# El-Fueradoro_Zuendbox.net
KiCad netlist of a schematic drawn in EAGLE
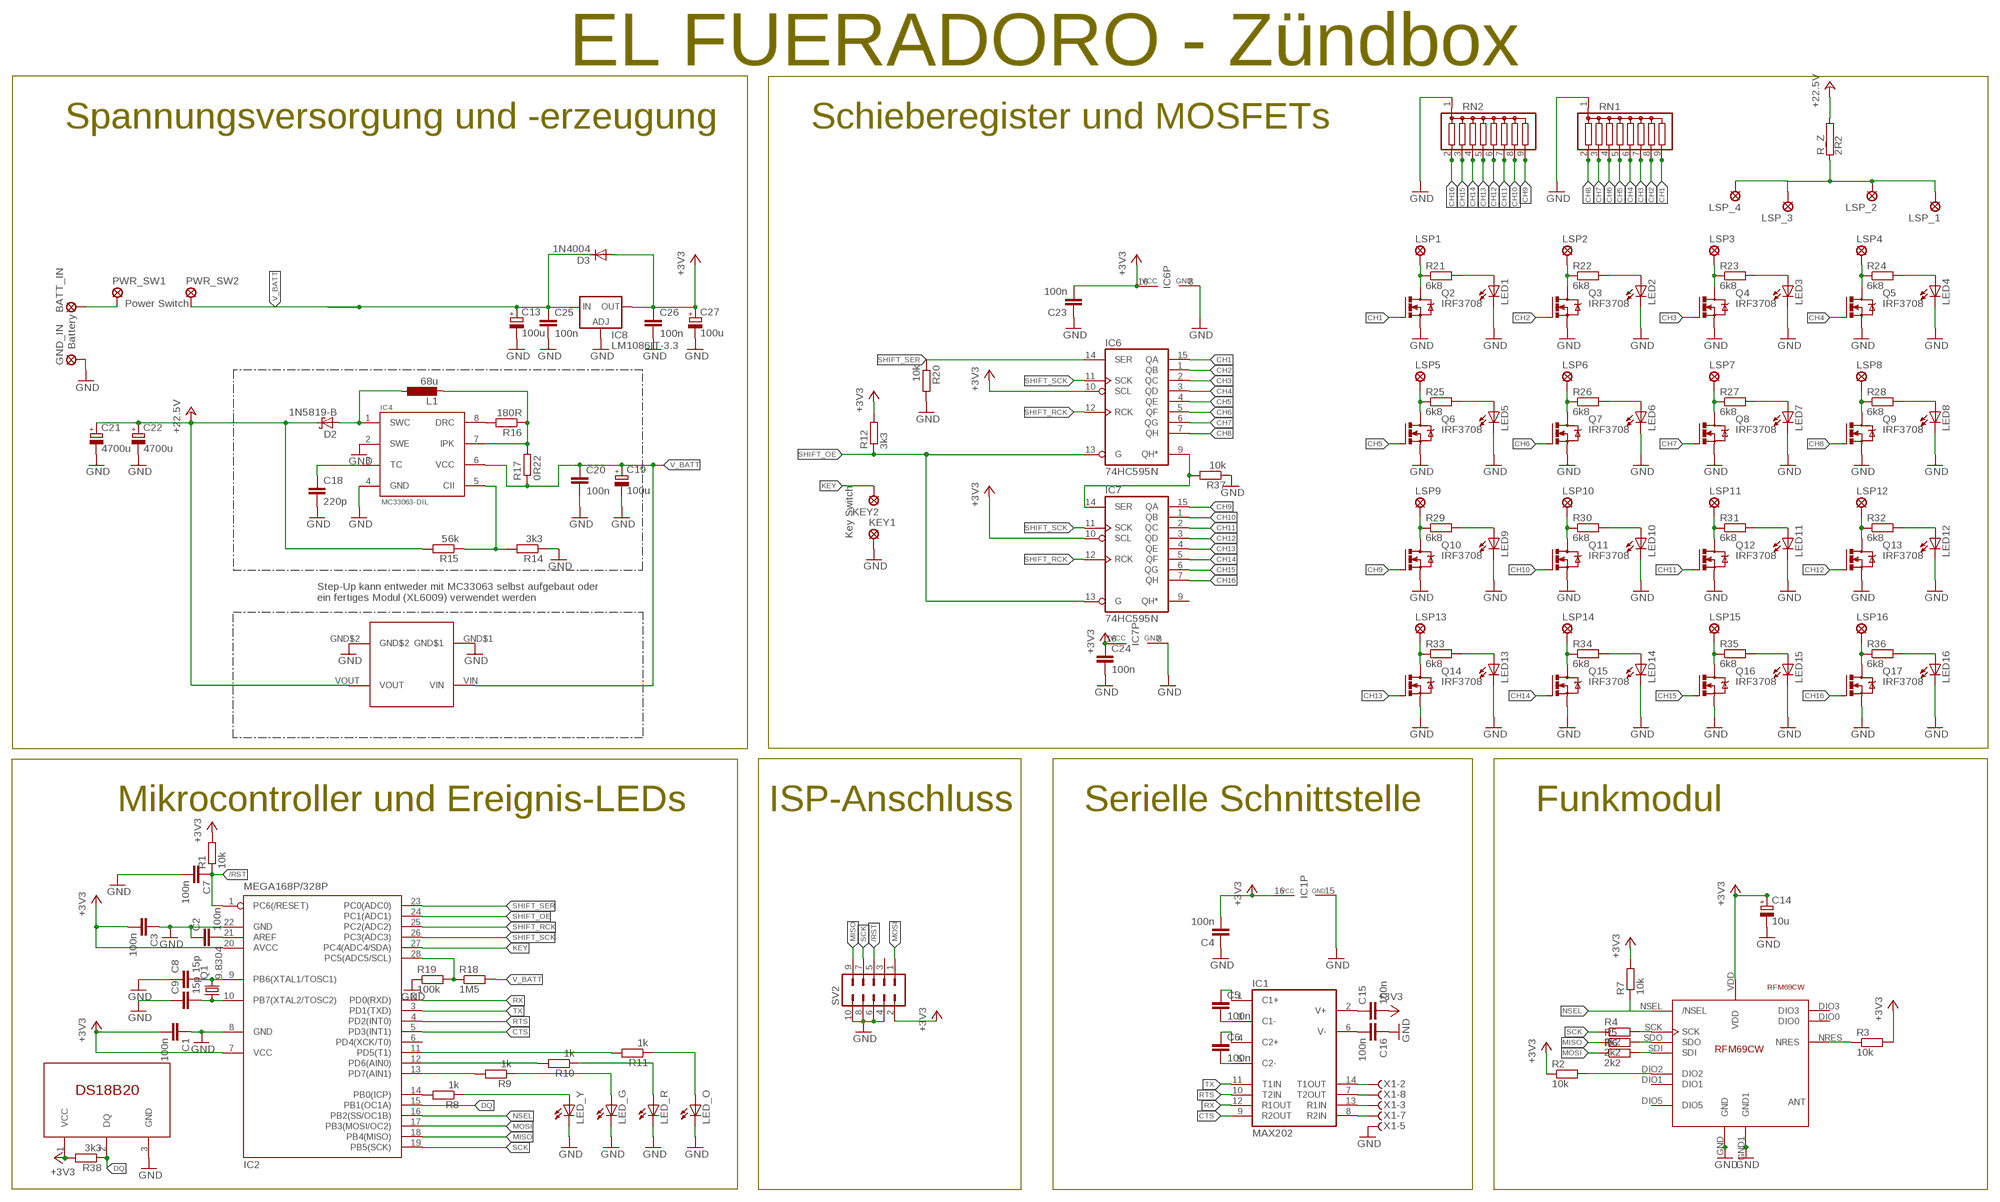
[diagram p0: schematic, sheet 1]

(export (version "E")
  (design (tool "Eeschema 10.0.6"))
  (components
    (comp (ref "BATT_IN")
      (value "LSP10")
      (footprint "eagle-import:LSP10")
      (libsource (lib "eagle-import") (part "LSP10"))
    )
    (comp (ref "C1")
      (value "100n")
      (footprint "eagle-import:C025-024X044")
      (libsource (lib "eagle-import") (part "C-EU025-024X044"))
    )
    (comp (ref "C2")
      (value "100n")
      (footprint "eagle-import:C025-024X044")
      (libsource (lib "eagle-import") (part "C-EU025-024X044"))
    )
    (comp (ref "C3")
      (value "100n")
      (footprint "eagle-import:C025-024X044")
      (libsource (lib "eagle-import") (part "C-EU025-024X044"))
    )
    (comp (ref "C4")
      (value "100n")
      (footprint "eagle-import:C025-024X044")
      (libsource (lib "eagle-import") (part "C-EU025-024X044"))
    )
    (comp (ref "C5")
      (value "100n")
      (footprint "eagle-import:C025-024X044")
      (libsource (lib "eagle-import") (part "C-EU025-024X044"))
    )
    (comp (ref "C6")
      (value "100n")
      (footprint "eagle-import:C025-024X044")
      (libsource (lib "eagle-import") (part "C-EU025-024X044"))
    )
    (comp (ref "C7")
      (value "100n")
      (footprint "eagle-import:C025-024X044")
      (libsource (lib "eagle-import") (part "C-EU025-024X044"))
    )
    (comp (ref "C8")
      (value "15p")
      (footprint "eagle-import:C025-024X044")
      (libsource (lib "eagle-import") (part "C-EU025-024X044"))
    )
    (comp (ref "C9")
      (value "15p")
      (footprint "eagle-import:C025-024X044")
      (libsource (lib "eagle-import") (part "C-EU025-024X044"))
    )
    (comp (ref "C13")
      (value "100u")
      (footprint "eagle-import:B45181A")
      (libsource (lib "eagle-import") (part "CPOL-EUB45181A"))
    )
    (comp (ref "C14")
      (value "10u")
      (footprint "eagle-import:B45181A")
      (libsource (lib "eagle-import") (part "CPOL-EUB45181A"))
    )
    (comp (ref "C15")
      (value "100n")
      (footprint "eagle-import:C025-024X044")
      (libsource (lib "eagle-import") (part "C-EU025-024X044"))
    )
    (comp (ref "C16")
      (value "100n")
      (footprint "eagle-import:C025-024X044")
      (libsource (lib "eagle-import") (part "C-EU025-024X044"))
    )
    (comp (ref "C18")
      (value "220p")
      (footprint "eagle-import:C025-024X044")
      (libsource (lib "eagle-import") (part "C-EU025-024X044"))
    )
    (comp (ref "C19")
      (value "100u")
      (footprint "eagle-import:E2,5-6E")
      (libsource (lib "eagle-import") (part "CPOL-EUE2,5-6E"))
    )
    (comp (ref "C20")
      (value "100n")
      (footprint "eagle-import:C025-024X044")
      (libsource (lib "eagle-import") (part "C-EU025-024X044"))
    )
    (comp (ref "C21")
      (value "4700u")
      (footprint "eagle-import:E7,5-18")
      (libsource (lib "eagle-import") (part "CPOL-EUE7.5-18"))
    )
    (comp (ref "C22")
      (value "4700u")
      (footprint "eagle-import:E7,5-18")
      (libsource (lib "eagle-import") (part "CPOL-EUE7.5-18"))
    )
    (comp (ref "C23")
      (value "100n")
      (footprint "eagle-import:C025-024X044")
      (libsource (lib "eagle-import") (part "C-EU025-024X044"))
    )
    (comp (ref "C24")
      (value "100n")
      (footprint "eagle-import:C025-024X044")
      (libsource (lib "eagle-import") (part "C-EU025-024X044"))
    )
    (comp (ref "C25")
      (value "100n")
      (footprint "eagle-import:C025-024X044")
      (libsource (lib "eagle-import") (part "C-EU025-024X044"))
    )
    (comp (ref "C26")
      (value "100n")
      (footprint "eagle-import:C025-024X044")
      (libsource (lib "eagle-import") (part "C-EU025-024X044"))
    )
    (comp (ref "C27")
      (value "100u")
      (footprint "eagle-import:B45181A")
      (libsource (lib "eagle-import") (part "CPOL-EUB45181A"))
    )
    (comp (ref "D2")
      (value "1N5819-B")
      (footprint "eagle-import:DO41-7.6")
      (libsource (lib "eagle-import") (part "1N5819-B"))
    )
    (comp (ref "D3")
      (value "1N4004")
      (footprint "eagle-import:DO41-10")
      (libsource (lib "eagle-import") (part "1N4004"))
    )
    (comp (ref "GND_IN")
      (value "LSP10")
      (footprint "eagle-import:LSP10")
      (libsource (lib "eagle-import") (part "LSP10"))
    )
    (comp (ref "IC1")
      (value "MAX202")
      (footprint "eagle-import:DIL16")
      (fields (field (name "MF") "MAXIM") (field (name "MPN") "MAX232ACPE+"))
      (libsource (lib "eagle-import") (part "MAX232"))
    )
    (comp (ref "IC2")
      (value "MEGA168P/328P")
      (footprint "eagle-import:DIL28-3")
      (libsource (lib "eagle-import") (part "MEGA8-P"))
    )
    (comp (ref "IC4")
      (value "MC33063-DIL")
      (footprint "eagle-import:DIL08")
      (libsource (lib "eagle-import") (part "MC34063-DIL"))
    )
    (comp (ref "IC6")
      (value "74HC595N")
      (footprint "eagle-import:DIL16")
      (libsource (lib "eagle-import") (part "74595NHC"))
    )
    (comp (ref "IC7")
      (value "74HC595N")
      (footprint "eagle-import:DIL16")
      (libsource (lib "eagle-import") (part "74595NHC"))
    )
    (comp (ref "IC8")
      (value "LM1086IT-3.3")
      (footprint "eagle-import:TO220L1")
      (libsource (lib "eagle-import") (part "LD117A?V"))
    )
    (comp (ref "KEY1")
      (value "LSP10")
      (footprint "eagle-import:LSP10")
      (libsource (lib "eagle-import") (part "LSP10"))
    )
    (comp (ref "KEY2")
      (value "LSP10")
      (footprint "eagle-import:LSP10")
      (libsource (lib "eagle-import") (part "LSP10"))
    )
    (comp (ref "L1")
      (value "68u")
      (footprint "eagle-import:0204_5")
      (libsource (lib "eagle-import") (part "L-EU0204/5"))
    )
    (comp (ref "LED1")
      (value "LED3MM")
      (footprint "eagle-import:LED3MM")
      (libsource (lib "eagle-import") (part "LED3MM"))
    )
    (comp (ref "LED2")
      (value "LED3MM")
      (footprint "eagle-import:LED3MM")
      (libsource (lib "eagle-import") (part "LED3MM"))
    )
    (comp (ref "LED3")
      (value "LED3MM")
      (footprint "eagle-import:LED3MM")
      (libsource (lib "eagle-import") (part "LED3MM"))
    )
    (comp (ref "LED4")
      (value "LED3MM")
      (footprint "eagle-import:LED3MM")
      (libsource (lib "eagle-import") (part "LED3MM"))
    )
    (comp (ref "LED5")
      (value "LED3MM")
      (footprint "eagle-import:LED3MM")
      (libsource (lib "eagle-import") (part "LED3MM"))
    )
    (comp (ref "LED6")
      (value "LED3MM")
      (footprint "eagle-import:LED3MM")
      (libsource (lib "eagle-import") (part "LED3MM"))
    )
    (comp (ref "LED7")
      (value "LED3MM")
      (footprint "eagle-import:LED3MM")
      (libsource (lib "eagle-import") (part "LED3MM"))
    )
    (comp (ref "LED8")
      (value "LED3MM")
      (footprint "eagle-import:LED3MM")
      (libsource (lib "eagle-import") (part "LED3MM"))
    )
    (comp (ref "LED9")
      (value "LED3MM")
      (footprint "eagle-import:LED3MM")
      (libsource (lib "eagle-import") (part "LED3MM"))
    )
    (comp (ref "LED10")
      (value "LED3MM")
      (footprint "eagle-import:LED3MM")
      (libsource (lib "eagle-import") (part "LED3MM"))
    )
    (comp (ref "LED11")
      (value "LED3MM")
      (footprint "eagle-import:LED3MM")
      (libsource (lib "eagle-import") (part "LED3MM"))
    )
    (comp (ref "LED12")
      (value "LED3MM")
      (footprint "eagle-import:LED3MM")
      (libsource (lib "eagle-import") (part "LED3MM"))
    )
    (comp (ref "LED13")
      (value "LED3MM")
      (footprint "eagle-import:LED3MM")
      (libsource (lib "eagle-import") (part "LED3MM"))
    )
    (comp (ref "LED14")
      (value "LED3MM")
      (footprint "eagle-import:LED3MM")
      (libsource (lib "eagle-import") (part "LED3MM"))
    )
    (comp (ref "LED15")
      (value "LED3MM")
      (footprint "eagle-import:LED3MM")
      (libsource (lib "eagle-import") (part "LED3MM"))
    )
    (comp (ref "LED16")
      (value "LED3MM")
      (footprint "eagle-import:LED3MM")
      (libsource (lib "eagle-import") (part "LED3MM"))
    )
    (comp (ref "LED_G")
      (value "LED5MM")
      (footprint "eagle-import:LED5MM")
      (libsource (lib "eagle-import") (part "LED5MM"))
    )
    (comp (ref "LED_O")
      (value "LED5MM")
      (footprint "eagle-import:LED5MM")
      (libsource (lib "eagle-import") (part "LED5MM"))
    )
    (comp (ref "LED_R")
      (value "LED5MM")
      (footprint "eagle-import:LED5MM")
      (libsource (lib "eagle-import") (part "LED5MM"))
    )
    (comp (ref "LED_Y")
      (value "LED5MM")
      (footprint "eagle-import:LED5MM")
      (libsource (lib "eagle-import") (part "LED5MM"))
    )
    (comp (ref "LSP1")
      (value "LSP11")
      (footprint "eagle-import:LSP11")
      (libsource (lib "eagle-import") (part "LSP11"))
    )
    (comp (ref "LSP2")
      (value "LSP11")
      (footprint "eagle-import:LSP11")
      (libsource (lib "eagle-import") (part "LSP11"))
    )
    (comp (ref "LSP3")
      (value "LSP11")
      (footprint "eagle-import:LSP11")
      (libsource (lib "eagle-import") (part "LSP11"))
    )
    (comp (ref "LSP4")
      (value "LSP11")
      (footprint "eagle-import:LSP11")
      (libsource (lib "eagle-import") (part "LSP11"))
    )
    (comp (ref "LSP5")
      (value "LSP11")
      (footprint "eagle-import:LSP11")
      (libsource (lib "eagle-import") (part "LSP11"))
    )
    (comp (ref "LSP6")
      (value "LSP11")
      (footprint "eagle-import:LSP11")
      (libsource (lib "eagle-import") (part "LSP11"))
    )
    (comp (ref "LSP7")
      (value "LSP11")
      (footprint "eagle-import:LSP11")
      (libsource (lib "eagle-import") (part "LSP11"))
    )
    (comp (ref "LSP8")
      (value "LSP11")
      (footprint "eagle-import:LSP11")
      (libsource (lib "eagle-import") (part "LSP11"))
    )
    (comp (ref "LSP9")
      (value "LSP11")
      (footprint "eagle-import:LSP11")
      (libsource (lib "eagle-import") (part "LSP11"))
    )
    (comp (ref "LSP10")
      (value "LSP11")
      (footprint "eagle-import:LSP11")
      (libsource (lib "eagle-import") (part "LSP11"))
    )
    (comp (ref "LSP11")
      (value "LSP11")
      (footprint "eagle-import:LSP11")
      (libsource (lib "eagle-import") (part "LSP11"))
    )
    (comp (ref "LSP12")
      (value "LSP11")
      (footprint "eagle-import:LSP11")
      (libsource (lib "eagle-import") (part "LSP11"))
    )
    (comp (ref "LSP13")
      (value "LSP11")
      (footprint "eagle-import:LSP11")
      (libsource (lib "eagle-import") (part "LSP11"))
    )
    (comp (ref "LSP14")
      (value "LSP11")
      (footprint "eagle-import:LSP11")
      (libsource (lib "eagle-import") (part "LSP11"))
    )
    (comp (ref "LSP15")
      (value "LSP11")
      (footprint "eagle-import:LSP11")
      (libsource (lib "eagle-import") (part "LSP11"))
    )
    (comp (ref "LSP16")
      (value "LSP11")
      (footprint "eagle-import:LSP11")
      (libsource (lib "eagle-import") (part "LSP11"))
    )
    (comp (ref "LSP_1")
      (value "LSP11")
      (footprint "eagle-import:LSP11")
      (libsource (lib "eagle-import") (part "LSP11"))
    )
    (comp (ref "LSP_2")
      (value "LSP11")
      (footprint "eagle-import:LSP11")
      (libsource (lib "eagle-import") (part "LSP11"))
    )
    (comp (ref "LSP_3")
      (value "LSP11")
      (footprint "eagle-import:LSP11")
      (libsource (lib "eagle-import") (part "LSP11"))
    )
    (comp (ref "LSP_4")
      (value "LSP11")
      (footprint "eagle-import:LSP11")
      (libsource (lib "eagle-import") (part "LSP11"))
    )
    (comp (ref "PWR_SW1")
      (value "LSP10")
      (footprint "eagle-import:LSP10")
      (libsource (lib "eagle-import") (part "LSP10"))
    )
    (comp (ref "PWR_SW2")
      (value "LSP10")
      (footprint "eagle-import:LSP10")
      (libsource (lib "eagle-import") (part "LSP10"))
    )
    (comp (ref "Q1")
      (value "9.8304")
      (footprint "eagle-import:HC49_S")
      (libsource (lib "eagle-import") (part "CRYSTALHC49S"))
    )
    (comp (ref "Q2")
      (value "IRF3708")
      (footprint "eagle-import:TO220BV")
      (libsource (lib "eagle-import") (part "IRF530"))
    )
    (comp (ref "Q3")
      (value "IRF3708")
      (footprint "eagle-import:TO220BV")
      (libsource (lib "eagle-import") (part "IRF530"))
    )
    (comp (ref "Q4")
      (value "IRF3708")
      (footprint "eagle-import:TO220BV")
      (libsource (lib "eagle-import") (part "IRF530"))
    )
    (comp (ref "Q5")
      (value "IRF3708")
      (footprint "eagle-import:TO220BV")
      (libsource (lib "eagle-import") (part "IRF530"))
    )
    (comp (ref "Q6")
      (value "IRF3708")
      (footprint "eagle-import:TO220BV")
      (libsource (lib "eagle-import") (part "IRF530"))
    )
    (comp (ref "Q7")
      (value "IRF3708")
      (footprint "eagle-import:TO220BV")
      (libsource (lib "eagle-import") (part "IRF530"))
    )
    (comp (ref "Q8")
      (value "IRF3708")
      (footprint "eagle-import:TO220BV")
      (libsource (lib "eagle-import") (part "IRF530"))
    )
    (comp (ref "Q9")
      (value "IRF3708")
      (footprint "eagle-import:TO220BV")
      (libsource (lib "eagle-import") (part "IRF530"))
    )
    (comp (ref "Q10")
      (value "IRF3708")
      (footprint "eagle-import:TO220BV")
      (libsource (lib "eagle-import") (part "IRF530"))
    )
    (comp (ref "Q11")
      (value "IRF3708")
      (footprint "eagle-import:TO220BV")
      (libsource (lib "eagle-import") (part "IRF530"))
    )
    (comp (ref "Q12")
      (value "IRF3708")
      (footprint "eagle-import:TO220BV")
      (libsource (lib "eagle-import") (part "IRF530"))
    )
    (comp (ref "Q13")
      (value "IRF3708")
      (footprint "eagle-import:TO220BV")
      (libsource (lib "eagle-import") (part "IRF530"))
    )
    (comp (ref "Q14")
      (value "IRF3708")
      (footprint "eagle-import:TO220BV")
      (libsource (lib "eagle-import") (part "IRF530"))
    )
    (comp (ref "Q15")
      (value "IRF3708")
      (footprint "eagle-import:TO220BV")
      (libsource (lib "eagle-import") (part "IRF530"))
    )
    (comp (ref "Q16")
      (value "IRF3708")
      (footprint "eagle-import:TO220BV")
      (libsource (lib "eagle-import") (part "IRF530"))
    )
    (comp (ref "Q17")
      (value "IRF3708")
      (footprint "eagle-import:TO220BV")
      (libsource (lib "eagle-import") (part "IRF530"))
    )
    (comp (ref "R1")
      (value "10k")
      (footprint "eagle-import:0207_10")
      (libsource (lib "eagle-import") (part "R-EU_0207/10"))
    )
    (comp (ref "R2")
      (value "10k")
      (footprint "eagle-import:0207_10")
      (libsource (lib "eagle-import") (part "R-EU_0207/10"))
    )
    (comp (ref "R3")
      (value "10k")
      (footprint "eagle-import:0207_10")
      (libsource (lib "eagle-import") (part "R-EU_0207/10"))
    )
    (comp (ref "R4")
      (value "2k2")
      (footprint "eagle-import:0207_10")
      (libsource (lib "eagle-import") (part "R-EU_0207/10"))
    )
    (comp (ref "R5")
      (value "2k2")
      (footprint "eagle-import:0207_10")
      (libsource (lib "eagle-import") (part "R-EU_0207/10"))
    )
    (comp (ref "R6")
      (value "2k2")
      (footprint "eagle-import:0207_10")
      (libsource (lib "eagle-import") (part "R-EU_0207/10"))
    )
    (comp (ref "R7")
      (value "10k")
      (footprint "eagle-import:0207_10")
      (libsource (lib "eagle-import") (part "R-EU_0207/10"))
    )
    (comp (ref "R8")
      (value "1k")
      (footprint "eagle-import:0207_10")
      (libsource (lib "eagle-import") (part "R-EU_0207/10"))
    )
    (comp (ref "R9")
      (value "1k")
      (footprint "eagle-import:0207_10")
      (libsource (lib "eagle-import") (part "R-EU_0207/10"))
    )
    (comp (ref "R10")
      (value "1k")
      (footprint "eagle-import:0207_10")
      (libsource (lib "eagle-import") (part "R-EU_0207/10"))
    )
    (comp (ref "R11")
      (value "1k")
      (footprint "eagle-import:0207_10")
      (libsource (lib "eagle-import") (part "R-EU_0207/10"))
    )
    (comp (ref "R12")
      (value "3k3")
      (footprint "eagle-import:0207_10")
      (libsource (lib "eagle-import") (part "R-EU_0207/10"))
    )
    (comp (ref "R14")
      (value "3k3")
      (footprint "eagle-import:0207_10")
      (libsource (lib "eagle-import") (part "R-EU_0207/10"))
    )
    (comp (ref "R15")
      (value "56k")
      (footprint "eagle-import:0207_10")
      (libsource (lib "eagle-import") (part "R-EU_0207/10"))
    )
    (comp (ref "R16")
      (value "180R")
      (footprint "eagle-import:0207_10")
      (libsource (lib "eagle-import") (part "R-EU_0207/10"))
    )
    (comp (ref "R17")
      (value "0R22")
      (footprint "eagle-import:0207_10")
      (libsource (lib "eagle-import") (part "R-EU_0207/10"))
    )
    (comp (ref "R18")
      (value "1M5")
      (footprint "eagle-import:0207_10")
      (libsource (lib "eagle-import") (part "R-EU_0207/10"))
    )
    (comp (ref "R19")
      (value "100k")
      (footprint "eagle-import:0207_10")
      (libsource (lib "eagle-import") (part "R-EU_0207/10"))
    )
    (comp (ref "R20")
      (value "10k")
      (footprint "eagle-import:0207_10")
      (libsource (lib "eagle-import") (part "R-EU_0207/10"))
    )
    (comp (ref "R21")
      (value "6k8")
      (footprint "eagle-import:0207_10")
      (libsource (lib "eagle-import") (part "R-EU_0207/10"))
    )
    (comp (ref "R22")
      (value "6k8")
      (footprint "eagle-import:0207_10")
      (libsource (lib "eagle-import") (part "R-EU_0207/10"))
    )
    (comp (ref "R23")
      (value "6k8")
      (footprint "eagle-import:0207_10")
      (libsource (lib "eagle-import") (part "R-EU_0207/10"))
    )
    (comp (ref "R24")
      (value "6k8")
      (footprint "eagle-import:0207_10")
      (libsource (lib "eagle-import") (part "R-EU_0207/10"))
    )
    (comp (ref "R25")
      (value "6k8")
      (footprint "eagle-import:0207_10")
      (libsource (lib "eagle-import") (part "R-EU_0207/10"))
    )
    (comp (ref "R26")
      (value "6k8")
      (footprint "eagle-import:0207_10")
      (libsource (lib "eagle-import") (part "R-EU_0207/10"))
    )
    (comp (ref "R27")
      (value "6k8")
      (footprint "eagle-import:0207_10")
      (libsource (lib "eagle-import") (part "R-EU_0207/10"))
    )
    (comp (ref "R28")
      (value "6k8")
      (footprint "eagle-import:0207_10")
      (libsource (lib "eagle-import") (part "R-EU_0207/10"))
    )
    (comp (ref "R29")
      (value "6k8")
      (footprint "eagle-import:0207_10")
      (libsource (lib "eagle-import") (part "R-EU_0207/10"))
    )
    (comp (ref "R30")
      (value "6k8")
      (footprint "eagle-import:0207_10")
      (libsource (lib "eagle-import") (part "R-EU_0207/10"))
    )
    (comp (ref "R31")
      (value "6k8")
      (footprint "eagle-import:0207_10")
      (libsource (lib "eagle-import") (part "R-EU_0207/10"))
    )
    (comp (ref "R32")
      (value "6k8")
      (footprint "eagle-import:0207_10")
      (libsource (lib "eagle-import") (part "R-EU_0207/10"))
    )
    (comp (ref "R33")
      (value "6k8")
      (footprint "eagle-import:0207_10")
      (libsource (lib "eagle-import") (part "R-EU_0207/10"))
    )
    (comp (ref "R34")
      (value "6k8")
      (footprint "eagle-import:0207_10")
      (libsource (lib "eagle-import") (part "R-EU_0207/10"))
    )
    (comp (ref "R35")
      (value "6k8")
      (footprint "eagle-import:0207_10")
      (libsource (lib "eagle-import") (part "R-EU_0207/10"))
    )
    (comp (ref "R36")
      (value "6k8")
      (footprint "eagle-import:0207_10")
      (libsource (lib "eagle-import") (part "R-EU_0207/10"))
    )
    (comp (ref "R37")
      (value "10k")
      (footprint "eagle-import:0207_10")
      (libsource (lib "eagle-import") (part "R-EU_0207/10"))
    )
    (comp (ref "R38")
      (value "3k3")
      (footprint "eagle-import:0207_10")
      (libsource (lib "eagle-import") (part "R-EU_0207/10"))
    )
    (comp (ref "RN1")
      (value "G08R")
      (footprint "eagle-import:SIL9")
      (libsource (lib "eagle-import") (part "G08R"))
    )
    (comp (ref "RN2")
      (value "G08R")
      (footprint "eagle-import:SIL9")
      (libsource (lib "eagle-import") (part "G08R"))
    )
    (comp (ref "R_Z")
      (value "2R2")
      (footprint "eagle-import:KH214R-8")
      (libsource (lib "eagle-import") (part "RKH214-8R"))
    )
    (comp (ref "SV2")
      (value "ML10")
      (footprint "eagle-import:ML10")
      (libsource (lib "eagle-import") (part "ML10"))
    )
    (comp (ref "U$2")
      (value "DS18B20")
      (footprint "eagle-import:TO92-LINE")
      (libsource (lib "eagle-import") (part "DS18B20"))
    )
    (comp (ref "U$3")
      (value "XL6009_MODULED")
      (footprint "eagle-import:XL6009_PACK")
      (libsource (lib "eagle-import") (part "XL6009_MODULED"))
    )
    (comp (ref "U$4")
      (value "RFM69CW")
      (footprint "eagle-import:RFM69CW")
      (libsource (lib "eagle-import") (part "RFM69CW"))
    )
    (comp (ref "X1")
      (value "F09HPS")
      (footprint "eagle-import:F09HP")
      (libsource (lib "eagle-import") (part "F09HPS"))
    )
  )
  (nets
    (net (code "1") (name "+3V3") (class "Default")
      (node (ref "C1") (pin "2") (pinfunction "2_2") (pintype "passive"))
      (node (ref "C14") (pin "+") (pinfunction "+_+") (pintype "passive"))
      (node (ref "C15") (pin "2") (pinfunction "2_2") (pintype "passive"))
      (node (ref "C23") (pin "2") (pinfunction "2_2") (pintype "passive"))
      (node (ref "C24") (pin "1") (pinfunction "1_1") (pintype "passive"))
      (node (ref "C26") (pin "1") (pinfunction "1_1") (pintype "passive"))
      (node (ref "C27") (pin "+") (pinfunction "+_+") (pintype "passive"))
      (node (ref "C3") (pin "2") (pinfunction "2_2") (pintype "passive"))
      (node (ref "C4") (pin "2") (pinfunction "2_2") (pintype "passive"))
      (node (ref "D3") (pin "A") (pinfunction "A_A") (pintype "passive"))
      (node (ref "IC1") (pin "16") (pinfunction "VCC_16") (pintype "power_in"))
      (node (ref "IC2") (pin "20") (pinfunction "AVCC_20") (pintype "power_in"))
      (node (ref "IC2") (pin "7") (pinfunction "VCC_7") (pintype "power_in"))
      (node (ref "IC6") (pin "10") (pinfunction "SCL_10") (pintype "input"))
      (node (ref "IC6") (pin "16") (pinfunction "VCC_16") (pintype "power_in"))
      (node (ref "IC7") (pin "10") (pinfunction "SCL_10") (pintype "input"))
      (node (ref "IC7") (pin "16") (pinfunction "VCC_16") (pintype "power_in"))
      (node (ref "IC8") (pin "2") (pinfunction "OUT_2") (pintype "passive"))
      (node (ref "R1") (pin "2") (pinfunction "2_2") (pintype "passive"))
      (node (ref "R12") (pin "2") (pinfunction "2_2") (pintype "passive"))
      (node (ref "R2") (pin "1") (pinfunction "1_1") (pintype "passive"))
      (node (ref "R3") (pin "2") (pinfunction "2_2") (pintype "passive"))
      (node (ref "R38") (pin "2") (pinfunction "2_2") (pintype "passive"))
      (node (ref "R7") (pin "2") (pinfunction "2_2") (pintype "passive"))
      (node (ref "SV2") (pin "2") (pinfunction "2_2") (pintype "passive"))
      (node (ref "U$2") (pin "1") (pinfunction "VCC_1") (pintype "power_in"))
      (node (ref "U$4") (pin "VDD") (pinfunction "VDD_VDD") (pintype "power_in"))
    )
    (net (code "2") (name "+22.5V") (class "Default")
      (node (ref "C21") (pin "+") (pinfunction "+_+") (pintype "passive"))
      (node (ref "C22") (pin "+") (pinfunction "+_+") (pintype "passive"))
      (node (ref "D2") (pin "C") (pinfunction "C_C") (pintype "passive"))
      (node (ref "R15") (pin "2") (pinfunction "2_2") (pintype "passive"))
      (node (ref "R_Z") (pin "2") (pinfunction "2_2") (pintype "passive"))
      (node (ref "U$3") (pin "VOUT") (pinfunction "VOUT_VOUT") (pintype "bidirectional"))
    )
    (net (code "3") (name "CH1") (class "Default")
      (node (ref "IC6") (pin "15") (pinfunction "QA_15") (pintype "tri_state"))
      (node (ref "Q2") (pin "G") (pinfunction "G_G") (pintype "passive"))
      (node (ref "RN1") (pin "9") (pinfunction "9_9") (pintype "passive"))
    )
    (net (code "4") (name "CH2") (class "Default")
      (node (ref "IC6") (pin "1") (pinfunction "QB_1") (pintype "tri_state"))
      (node (ref "Q3") (pin "G") (pinfunction "G_G") (pintype "passive"))
      (node (ref "RN1") (pin "8") (pinfunction "8_8") (pintype "passive"))
    )
    (net (code "5") (name "CH3") (class "Default")
      (node (ref "IC6") (pin "2") (pinfunction "QC_2") (pintype "tri_state"))
      (node (ref "Q4") (pin "G") (pinfunction "G_G") (pintype "passive"))
      (node (ref "RN1") (pin "7") (pinfunction "7_7") (pintype "passive"))
    )
    (net (code "6") (name "CH4") (class "Default")
      (node (ref "IC6") (pin "3") (pinfunction "QD_3") (pintype "tri_state"))
      (node (ref "Q5") (pin "G") (pinfunction "G_G") (pintype "passive"))
      (node (ref "RN1") (pin "6") (pinfunction "6_6") (pintype "passive"))
    )
    (net (code "7") (name "CH5") (class "Default")
      (node (ref "IC6") (pin "4") (pinfunction "QE_4") (pintype "tri_state"))
      (node (ref "Q6") (pin "G") (pinfunction "G_G") (pintype "passive"))
      (node (ref "RN1") (pin "5") (pinfunction "5_5") (pintype "passive"))
    )
    (net (code "8") (name "CH6") (class "Default")
      (node (ref "IC6") (pin "5") (pinfunction "QF_5") (pintype "tri_state"))
      (node (ref "Q7") (pin "G") (pinfunction "G_G") (pintype "passive"))
      (node (ref "RN1") (pin "4") (pinfunction "4_4") (pintype "passive"))
    )
    (net (code "9") (name "CH7") (class "Default")
      (node (ref "IC6") (pin "6") (pinfunction "QG_6") (pintype "tri_state"))
      (node (ref "Q8") (pin "G") (pinfunction "G_G") (pintype "passive"))
      (node (ref "RN1") (pin "3") (pinfunction "3_3") (pintype "passive"))
    )
    (net (code "10") (name "CH8") (class "Default")
      (node (ref "IC6") (pin "7") (pinfunction "QH_7") (pintype "tri_state"))
      (node (ref "Q9") (pin "G") (pinfunction "G_G") (pintype "passive"))
      (node (ref "RN1") (pin "2") (pinfunction "2_2") (pintype "passive"))
    )
    (net (code "11") (name "CH9") (class "Default")
      (node (ref "IC7") (pin "15") (pinfunction "QA_15") (pintype "tri_state"))
      (node (ref "Q10") (pin "G") (pinfunction "G_G") (pintype "passive"))
      (node (ref "RN2") (pin "9") (pinfunction "9_9") (pintype "passive"))
    )
    (net (code "12") (name "CH10") (class "Default")
      (node (ref "IC7") (pin "1") (pinfunction "QB_1") (pintype "tri_state"))
      (node (ref "Q11") (pin "G") (pinfunction "G_G") (pintype "passive"))
      (node (ref "RN2") (pin "8") (pinfunction "8_8") (pintype "passive"))
    )
    (net (code "13") (name "CH11") (class "Default")
      (node (ref "IC7") (pin "2") (pinfunction "QC_2") (pintype "tri_state"))
      (node (ref "Q12") (pin "G") (pinfunction "G_G") (pintype "passive"))
      (node (ref "RN2") (pin "7") (pinfunction "7_7") (pintype "passive"))
    )
    (net (code "14") (name "CH12") (class "Default")
      (node (ref "IC7") (pin "3") (pinfunction "QD_3") (pintype "tri_state"))
      (node (ref "Q13") (pin "G") (pinfunction "G_G") (pintype "passive"))
      (node (ref "RN2") (pin "6") (pinfunction "6_6") (pintype "passive"))
    )
    (net (code "15") (name "CH13") (class "Default")
      (node (ref "IC7") (pin "4") (pinfunction "QE_4") (pintype "tri_state"))
      (node (ref "Q14") (pin "G") (pinfunction "G_G") (pintype "passive"))
      (node (ref "RN2") (pin "5") (pinfunction "5_5") (pintype "passive"))
    )
    (net (code "16") (name "CH14") (class "Default")
      (node (ref "IC7") (pin "5") (pinfunction "QF_5") (pintype "tri_state"))
      (node (ref "Q15") (pin "G") (pinfunction "G_G") (pintype "passive"))
      (node (ref "RN2") (pin "4") (pinfunction "4_4") (pintype "passive"))
    )
    (net (code "17") (name "CH15") (class "Default")
      (node (ref "IC7") (pin "6") (pinfunction "QG_6") (pintype "tri_state"))
      (node (ref "Q16") (pin "G") (pinfunction "G_G") (pintype "passive"))
      (node (ref "RN2") (pin "3") (pinfunction "3_3") (pintype "passive"))
    )
    (net (code "18") (name "CH16") (class "Default")
      (node (ref "IC7") (pin "7") (pinfunction "QH_7") (pintype "tri_state"))
      (node (ref "Q17") (pin "G") (pinfunction "G_G") (pintype "passive"))
      (node (ref "RN2") (pin "2") (pinfunction "2_2") (pintype "passive"))
    )
    (net (code "19") (name "CTS") (class "Default")
      (node (ref "IC1") (pin "9") (pinfunction "R2OUT_9") (pintype "output"))
      (node (ref "IC2") (pin "5") (pinfunction "PD3(INT1)_5") (pintype "bidirectional"))
    )
    (net (code "20") (name "DQ") (class "Default")
      (node (ref "IC2") (pin "15") (pinfunction "PB1(OC1A)_15") (pintype "bidirectional"))
      (node (ref "R38") (pin "1") (pinfunction "1_1") (pintype "passive"))
      (node (ref "U$2") (pin "2") (pinfunction "DQ_2") (pintype "bidirectional"))
    )
    (net (code "21") (name "GND") (class "Default")
      (node (ref "C1") (pin "1") (pinfunction "1_1") (pintype "passive"))
      (node (ref "C13") (pin "-") (pinfunction "-_-") (pintype "passive"))
      (node (ref "C14") (pin "-") (pinfunction "-_-") (pintype "passive"))
      (node (ref "C16") (pin "1") (pinfunction "1_1") (pintype "passive"))
      (node (ref "C18") (pin "2") (pinfunction "2_2") (pintype "passive"))
      (node (ref "C19") (pin "-") (pinfunction "-_-") (pintype "passive"))
      (node (ref "C2") (pin "1") (pinfunction "1_1") (pintype "passive"))
      (node (ref "C20") (pin "2") (pinfunction "2_2") (pintype "passive"))
      (node (ref "C21") (pin "-") (pinfunction "-_-") (pintype "passive"))
      (node (ref "C22") (pin "-") (pinfunction "-_-") (pintype "passive"))
      (node (ref "C23") (pin "1") (pinfunction "1_1") (pintype "passive"))
      (node (ref "C24") (pin "2") (pinfunction "2_2") (pintype "passive"))
      (node (ref "C25") (pin "2") (pinfunction "2_2") (pintype "passive"))
      (node (ref "C26") (pin "2") (pinfunction "2_2") (pintype "passive"))
      (node (ref "C27") (pin "-") (pinfunction "-_-") (pintype "passive"))
      (node (ref "C3") (pin "1") (pinfunction "1_1") (pintype "passive"))
      (node (ref "C4") (pin "1") (pinfunction "1_1") (pintype "passive"))
      (node (ref "C7") (pin "2") (pinfunction "2_2") (pintype "passive"))
      (node (ref "C8") (pin "1") (pinfunction "1_1") (pintype "passive"))
      (node (ref "C9") (pin "1") (pinfunction "1_1") (pintype "passive"))
      (node (ref "GND_IN") (pin "MP") (pinfunction "MP_MP") (pintype "passive"))
      (node (ref "IC1") (pin "15") (pinfunction "GND_15") (pintype "power_in"))
      (node (ref "IC2") (pin "22") (pinfunction "GND_22") (pintype "power_in"))
      (node (ref "IC2") (pin "8") (pinfunction "GND_8") (pintype "power_in"))
      (node (ref "IC4") (pin "2") (pinfunction "SWE_2") (pintype "bidirectional"))
      (node (ref "IC4") (pin "4") (pinfunction "GND_4") (pintype "power_in"))
      (node (ref "IC6") (pin "8") (pinfunction "GND_8") (pintype "power_in"))
      (node (ref "IC7") (pin "8") (pinfunction "GND_8") (pintype "power_in"))
      (node (ref "IC8") (pin "1") (pinfunction "ADJ_1") (pintype "input"))
      (node (ref "KEY1") (pin "MP") (pinfunction "MP_MP") (pintype "passive"))
      (node (ref "LED1") (pin "K") (pinfunction "C_K") (pintype "passive"))
      (node (ref "LED10") (pin "K") (pinfunction "C_K") (pintype "passive"))
      (node (ref "LED11") (pin "K") (pinfunction "C_K") (pintype "passive"))
      (node (ref "LED12") (pin "K") (pinfunction "C_K") (pintype "passive"))
      (node (ref "LED13") (pin "K") (pinfunction "C_K") (pintype "passive"))
      (node (ref "LED14") (pin "K") (pinfunction "C_K") (pintype "passive"))
      (node (ref "LED15") (pin "K") (pinfunction "C_K") (pintype "passive"))
      (node (ref "LED16") (pin "K") (pinfunction "C_K") (pintype "passive"))
      (node (ref "LED2") (pin "K") (pinfunction "C_K") (pintype "passive"))
      (node (ref "LED3") (pin "K") (pinfunction "C_K") (pintype "passive"))
      (node (ref "LED4") (pin "K") (pinfunction "C_K") (pintype "passive"))
      (node (ref "LED5") (pin "K") (pinfunction "C_K") (pintype "passive"))
      (node (ref "LED6") (pin "K") (pinfunction "C_K") (pintype "passive"))
      (node (ref "LED7") (pin "K") (pinfunction "C_K") (pintype "passive"))
      (node (ref "LED8") (pin "K") (pinfunction "C_K") (pintype "passive"))
      (node (ref "LED9") (pin "K") (pinfunction "C_K") (pintype "passive"))
      (node (ref "LED_G") (pin "K") (pinfunction "C_K") (pintype "passive"))
      (node (ref "LED_O") (pin "K") (pinfunction "C_K") (pintype "passive"))
      (node (ref "LED_R") (pin "K") (pinfunction "C_K") (pintype "passive"))
      (node (ref "LED_Y") (pin "K") (pinfunction "C_K") (pintype "passive"))
      (node (ref "Q10") (pin "S") (pinfunction "S_S") (pintype "passive"))
      (node (ref "Q11") (pin "S") (pinfunction "S_S") (pintype "passive"))
      (node (ref "Q12") (pin "S") (pinfunction "S_S") (pintype "passive"))
      (node (ref "Q13") (pin "S") (pinfunction "S_S") (pintype "passive"))
      (node (ref "Q14") (pin "S") (pinfunction "S_S") (pintype "passive"))
      (node (ref "Q15") (pin "S") (pinfunction "S_S") (pintype "passive"))
      (node (ref "Q16") (pin "S") (pinfunction "S_S") (pintype "passive"))
      (node (ref "Q17") (pin "S") (pinfunction "S_S") (pintype "passive"))
      (node (ref "Q2") (pin "S") (pinfunction "S_S") (pintype "passive"))
      (node (ref "Q3") (pin "S") (pinfunction "S_S") (pintype "passive"))
      (node (ref "Q4") (pin "S") (pinfunction "S_S") (pintype "passive"))
      (node (ref "Q5") (pin "S") (pinfunction "S_S") (pintype "passive"))
      (node (ref "Q6") (pin "S") (pinfunction "S_S") (pintype "passive"))
      (node (ref "Q7") (pin "S") (pinfunction "S_S") (pintype "passive"))
      (node (ref "Q8") (pin "S") (pinfunction "S_S") (pintype "passive"))
      (node (ref "Q9") (pin "S") (pinfunction "S_S") (pintype "passive"))
      (node (ref "R14") (pin "1") (pinfunction "1_1") (pintype "passive"))
      (node (ref "R19") (pin "1") (pinfunction "1_1") (pintype "passive"))
      (node (ref "R20") (pin "2") (pinfunction "2_2") (pintype "passive"))
      (node (ref "R37") (pin "1") (pinfunction "1_1") (pintype "passive"))
      (node (ref "RN1") (pin "1") (pinfunction "1_1") (pintype "passive"))
      (node (ref "RN2") (pin "1") (pinfunction "1_1") (pintype "passive"))
      (node (ref "SV2") (pin "10") (pinfunction "10_10") (pintype "passive"))
      (node (ref "SV2") (pin "4") (pinfunction "4_4") (pintype "passive"))
      (node (ref "SV2") (pin "6") (pinfunction "6_6") (pintype "passive"))
      (node (ref "SV2") (pin "8") (pinfunction "8_8") (pintype "passive"))
      (node (ref "U$2") (pin "3") (pinfunction "GND_3") (pintype "power_in"))
      (node (ref "U$3") (pin "GND$1") (pinfunction "GND$1_GND$1") (pintype "bidirectional"))
      (node (ref "U$3") (pin "GND$2") (pinfunction "GND$2_GND$2") (pintype "bidirectional"))
      (node (ref "U$4") (pin "GND") (pinfunction "GND_GND") (pintype "power_in"))
      (node (ref "U$4") (pin "GND1") (pinfunction "GND1_GND1") (pintype "power_in"))
      (node (ref "X1") (pin "5") (pinfunction "F_5") (pintype "passive"))
    )
    (net (code "22") (name "KEY") (class "Default")
      (node (ref "IC2") (pin "27") (pinfunction "PC4(ADC4/SDA)_27") (pintype "bidirectional"))
      (node (ref "KEY2") (pin "MP") (pinfunction "MP_MP") (pintype "passive"))
    )
    (net (code "23") (name "MISO") (class "Default")
      (node (ref "IC2") (pin "18") (pinfunction "PB4(MISO)_18") (pintype "bidirectional"))
      (node (ref "R5") (pin "1") (pinfunction "1_1") (pintype "passive"))
      (node (ref "SV2") (pin "9") (pinfunction "9_9") (pintype "passive"))
    )
    (net (code "24") (name "MOSI") (class "Default")
      (node (ref "IC2") (pin "17") (pinfunction "PB3(MOSI/OC2)_17") (pintype "bidirectional"))
      (node (ref "R6") (pin "1") (pinfunction "1_1") (pintype "passive"))
      (node (ref "SV2") (pin "1") (pinfunction "1_1") (pintype "passive"))
    )
    (net (code "25") (name "NSEL") (class "Default")
      (node (ref "IC2") (pin "16") (pinfunction "PB2(SS/OC1B)_16") (pintype "bidirectional"))
      (node (ref "R7") (pin "1") (pinfunction "1_1") (pintype "passive"))
      (node (ref "U$4") (pin "NSEL") (pinfunction "/NSEL_NSEL") (pintype "input"))
    )
    (net (code "26") (name "Net-(BATT_IN-PadMP)") (class "Default")
      (node (ref "BATT_IN") (pin "MP") (pinfunction "MP_MP") (pintype "passive"))
      (node (ref "PWR_SW1") (pin "MP") (pinfunction "MP_MP") (pintype "passive"))
    )
    (net (code "27") (name "Net-(IC1A-C1+)") (class "Default")
      (node (ref "C5") (pin "1") (pinfunction "1_1") (pintype "passive"))
      (node (ref "IC1") (pin "1") (pinfunction "C1+_1") (pintype "bidirectional"))
    )
    (net (code "28") (name "Net-(IC1A-C1-)") (class "Default")
      (node (ref "C5") (pin "2") (pinfunction "2_2") (pintype "passive"))
      (node (ref "IC1") (pin "3") (pinfunction "C1-_3") (pintype "bidirectional"))
    )
    (net (code "29") (name "Net-(IC1A-C2+)") (class "Default")
      (node (ref "C6") (pin "1") (pinfunction "1_1") (pintype "passive"))
      (node (ref "IC1") (pin "4") (pinfunction "C2+_4") (pintype "bidirectional"))
    )
    (net (code "30") (name "Net-(IC1A-C2-)") (class "Default")
      (node (ref "C6") (pin "2") (pinfunction "2_2") (pintype "passive"))
      (node (ref "IC1") (pin "5") (pinfunction "C2-_5") (pintype "bidirectional"))
    )
    (net (code "31") (name "Net-(IC1A-R1IN)") (class "Default")
      (node (ref "IC1") (pin "13") (pinfunction "R1IN_13") (pintype "input"))
      (node (ref "X1") (pin "3") (pinfunction "F_3") (pintype "passive"))
    )
    (net (code "32") (name "Net-(IC1A-R2IN)") (class "Default")
      (node (ref "IC1") (pin "8") (pinfunction "R2IN_8") (pintype "input"))
      (node (ref "X1") (pin "7") (pinfunction "F_7") (pintype "passive"))
    )
    (net (code "33") (name "Net-(IC1A-T1OUT)") (class "Default")
      (node (ref "IC1") (pin "14") (pinfunction "T1OUT_14") (pintype "output"))
      (node (ref "X1") (pin "2") (pinfunction "F_2") (pintype "passive"))
    )
    (net (code "34") (name "Net-(IC1A-T2OUT)") (class "Default")
      (node (ref "IC1") (pin "7") (pinfunction "T2OUT_7") (pintype "output"))
      (node (ref "X1") (pin "8") (pinfunction "F_8") (pintype "passive"))
    )
    (net (code "35") (name "Net-(IC1A-V+)") (class "Default")
      (node (ref "C15") (pin "1") (pinfunction "1_1") (pintype "passive"))
      (node (ref "IC1") (pin "2") (pinfunction "V+_2") (pintype "bidirectional"))
    )
    (net (code "36") (name "Net-(IC1A-V-)") (class "Default")
      (node (ref "C16") (pin "2") (pinfunction "2_2") (pintype "passive"))
      (node (ref "IC1") (pin "6") (pinfunction "V-_6") (pintype "bidirectional"))
    )
    (net (code "37") (name "Net-(IC2-AREF)") (class "Default")
      (node (ref "C2") (pin "2") (pinfunction "2_2") (pintype "passive"))
      (node (ref "IC2") (pin "21") (pinfunction "AREF_21") (pintype "passive"))
    )
    (net (code "38") (name "Net-(IC2-PB0(ICP))") (class "Default")
      (node (ref "IC2") (pin "14") (pinfunction "PB0(ICP)_14") (pintype "bidirectional"))
      (node (ref "R8") (pin "2") (pinfunction "2_2") (pintype "passive"))
    )
    (net (code "39") (name "Net-(IC2-PB6(XTAL1{slash}TOSC1))") (class "Default")
      (node (ref "C8") (pin "2") (pinfunction "2_2") (pintype "passive"))
      (node (ref "IC2") (pin "9") (pinfunction "PB6(XTAL1/TOSC1)_9") (pintype "bidirectional"))
      (node (ref "Q1") (pin "2") (pinfunction "2_2") (pintype "passive"))
    )
    (net (code "40") (name "Net-(IC2-PB7(XTAL2{slash}TOSC2))") (class "Default")
      (node (ref "C9") (pin "2") (pinfunction "2_2") (pintype "passive"))
      (node (ref "IC2") (pin "10") (pinfunction "PB7(XTAL2/TOSC2)_10") (pintype "bidirectional"))
      (node (ref "Q1") (pin "1") (pinfunction "1_1") (pintype "passive"))
    )
    (net (code "41") (name "Net-(IC2-PC5(ADC5{slash}SCL))") (class "Default")
      (node (ref "IC2") (pin "28") (pinfunction "PC5(ADC5/SCL)_28") (pintype "bidirectional"))
      (node (ref "R18") (pin "1") (pinfunction "1_1") (pintype "passive"))
      (node (ref "R19") (pin "2") (pinfunction "2_2") (pintype "passive"))
    )
    (net (code "42") (name "Net-(IC2-PD5(T1))") (class "Default")
      (node (ref "IC2") (pin "11") (pinfunction "PD5(T1)_11") (pintype "bidirectional"))
      (node (ref "R11") (pin "2") (pinfunction "2_2") (pintype "passive"))
    )
    (net (code "43") (name "Net-(IC2-PD6(AIN0))") (class "Default")
      (node (ref "IC2") (pin "12") (pinfunction "PD6(AIN0)_12") (pintype "bidirectional"))
      (node (ref "R10") (pin "2") (pinfunction "2_2") (pintype "passive"))
    )
    (net (code "44") (name "Net-(IC2-PD7(AIN1))") (class "Default")
      (node (ref "IC2") (pin "13") (pinfunction "PD7(AIN1)_13") (pintype "bidirectional"))
      (node (ref "R9") (pin "2") (pinfunction "2_2") (pintype "passive"))
    )
    (net (code "45") (name "Net-(IC4-CII)") (class "Default")
      (node (ref "IC4") (pin "5") (pinfunction "CII_5") (pintype "bidirectional"))
      (node (ref "R14") (pin "2") (pinfunction "2_2") (pintype "passive"))
      (node (ref "R15") (pin "1") (pinfunction "1_1") (pintype "passive"))
    )
    (net (code "46") (name "Net-(IC4-DRC)") (class "Default")
      (node (ref "IC4") (pin "8") (pinfunction "DRC_8") (pintype "bidirectional"))
      (node (ref "R16") (pin "2") (pinfunction "2_2") (pintype "passive"))
    )
    (net (code "47") (name "Net-(IC4-IPK)") (class "Default")
      (node (ref "IC4") (pin "7") (pinfunction "IPK_7") (pintype "bidirectional"))
      (node (ref "L1") (pin "2") (pinfunction "2_2") (pintype "passive"))
      (node (ref "R16") (pin "1") (pinfunction "1_1") (pintype "passive"))
      (node (ref "R17") (pin "2") (pinfunction "2_2") (pintype "passive"))
    )
    (net (code "48") (name "Net-(IC4-SWC)") (class "Default")
      (node (ref "D2") (pin "A") (pinfunction "A_A") (pintype "passive"))
      (node (ref "IC4") (pin "1") (pinfunction "SWC_1") (pintype "bidirectional"))
      (node (ref "L1") (pin "1") (pinfunction "1_1") (pintype "passive"))
    )
    (net (code "49") (name "Net-(IC4-TC)") (class "Default")
      (node (ref "C18") (pin "1") (pinfunction "1_1") (pintype "passive"))
      (node (ref "IC4") (pin "3") (pinfunction "TC_3") (pintype "bidirectional"))
    )
    (net (code "50") (name "Net-(IC6A-QH*)") (class "Default")
      (node (ref "IC6") (pin "9") (pinfunction "QH*_9") (pintype "tri_state"))
      (node (ref "IC7") (pin "14") (pinfunction "SER_14") (pintype "input"))
      (node (ref "R37") (pin "2") (pinfunction "2_2") (pintype "passive"))
    )
    (net (code "51") (name "Net-(LED1-PadA)") (class "Default")
      (node (ref "LED1") (pin "A") (pinfunction "A_A") (pintype "passive"))
      (node (ref "R21") (pin "2") (pinfunction "2_2") (pintype "passive"))
    )
    (net (code "52") (name "Net-(LED2-PadA)") (class "Default")
      (node (ref "LED2") (pin "A") (pinfunction "A_A") (pintype "passive"))
      (node (ref "R22") (pin "2") (pinfunction "2_2") (pintype "passive"))
    )
    (net (code "53") (name "Net-(LED3-PadA)") (class "Default")
      (node (ref "LED3") (pin "A") (pinfunction "A_A") (pintype "passive"))
      (node (ref "R23") (pin "2") (pinfunction "2_2") (pintype "passive"))
    )
    (net (code "54") (name "Net-(LED4-PadA)") (class "Default")
      (node (ref "LED4") (pin "A") (pinfunction "A_A") (pintype "passive"))
      (node (ref "R24") (pin "2") (pinfunction "2_2") (pintype "passive"))
    )
    (net (code "55") (name "Net-(LED5-PadA)") (class "Default")
      (node (ref "LED5") (pin "A") (pinfunction "A_A") (pintype "passive"))
      (node (ref "R25") (pin "2") (pinfunction "2_2") (pintype "passive"))
    )
    (net (code "56") (name "Net-(LED6-PadA)") (class "Default")
      (node (ref "LED6") (pin "A") (pinfunction "A_A") (pintype "passive"))
      (node (ref "R26") (pin "2") (pinfunction "2_2") (pintype "passive"))
    )
    (net (code "57") (name "Net-(LED7-PadA)") (class "Default")
      (node (ref "LED7") (pin "A") (pinfunction "A_A") (pintype "passive"))
      (node (ref "R27") (pin "2") (pinfunction "2_2") (pintype "passive"))
    )
    (net (code "58") (name "Net-(LED8-PadA)") (class "Default")
      (node (ref "LED8") (pin "A") (pinfunction "A_A") (pintype "passive"))
      (node (ref "R28") (pin "2") (pinfunction "2_2") (pintype "passive"))
    )
    (net (code "59") (name "Net-(LED9-PadA)") (class "Default")
      (node (ref "LED9") (pin "A") (pinfunction "A_A") (pintype "passive"))
      (node (ref "R29") (pin "2") (pinfunction "2_2") (pintype "passive"))
    )
    (net (code "60") (name "Net-(LED10-PadA)") (class "Default")
      (node (ref "LED10") (pin "A") (pinfunction "A_A") (pintype "passive"))
      (node (ref "R30") (pin "2") (pinfunction "2_2") (pintype "passive"))
    )
    (net (code "61") (name "Net-(LED11-PadA)") (class "Default")
      (node (ref "LED11") (pin "A") (pinfunction "A_A") (pintype "passive"))
      (node (ref "R31") (pin "2") (pinfunction "2_2") (pintype "passive"))
    )
    (net (code "62") (name "Net-(LED12-PadA)") (class "Default")
      (node (ref "LED12") (pin "A") (pinfunction "A_A") (pintype "passive"))
      (node (ref "R32") (pin "2") (pinfunction "2_2") (pintype "passive"))
    )
    (net (code "63") (name "Net-(LED13-PadA)") (class "Default")
      (node (ref "LED13") (pin "A") (pinfunction "A_A") (pintype "passive"))
      (node (ref "R33") (pin "2") (pinfunction "2_2") (pintype "passive"))
    )
    (net (code "64") (name "Net-(LED14-PadA)") (class "Default")
      (node (ref "LED14") (pin "A") (pinfunction "A_A") (pintype "passive"))
      (node (ref "R34") (pin "2") (pinfunction "2_2") (pintype "passive"))
    )
    (net (code "65") (name "Net-(LED15-PadA)") (class "Default")
      (node (ref "LED15") (pin "A") (pinfunction "A_A") (pintype "passive"))
      (node (ref "R35") (pin "2") (pinfunction "2_2") (pintype "passive"))
    )
    (net (code "66") (name "Net-(LED16-PadA)") (class "Default")
      (node (ref "LED16") (pin "A") (pinfunction "A_A") (pintype "passive"))
      (node (ref "R36") (pin "2") (pinfunction "2_2") (pintype "passive"))
    )
    (net (code "67") (name "Net-(LED_G-PadA)") (class "Default")
      (node (ref "LED_G") (pin "A") (pinfunction "A_A") (pintype "passive"))
      (node (ref "R9") (pin "1") (pinfunction "1_1") (pintype "passive"))
    )
    (net (code "68") (name "Net-(LED_O-PadA)") (class "Default")
      (node (ref "LED_O") (pin "A") (pinfunction "A_A") (pintype "passive"))
      (node (ref "R11") (pin "1") (pinfunction "1_1") (pintype "passive"))
    )
    (net (code "69") (name "Net-(LED_R-PadA)") (class "Default")
      (node (ref "LED_R") (pin "A") (pinfunction "A_A") (pintype "passive"))
      (node (ref "R10") (pin "1") (pinfunction "1_1") (pintype "passive"))
    )
    (net (code "70") (name "Net-(LED_Y-PadA)") (class "Default")
      (node (ref "LED_Y") (pin "A") (pinfunction "A_A") (pintype "passive"))
      (node (ref "R8") (pin "1") (pinfunction "1_1") (pintype "passive"))
    )
    (net (code "71") (name "Net-(LSP1-PadMP)") (class "Default")
      (node (ref "LSP1") (pin "MP") (pinfunction "MP_MP") (pintype "passive"))
      (node (ref "Q2") (pin "D") (pinfunction "D_D") (pintype "passive"))
      (node (ref "R21") (pin "1") (pinfunction "1_1") (pintype "passive"))
    )
    (net (code "72") (name "Net-(LSP2-PadMP)") (class "Default")
      (node (ref "LSP2") (pin "MP") (pinfunction "MP_MP") (pintype "passive"))
      (node (ref "Q3") (pin "D") (pinfunction "D_D") (pintype "passive"))
      (node (ref "R22") (pin "1") (pinfunction "1_1") (pintype "passive"))
    )
    (net (code "73") (name "Net-(LSP3-PadMP)") (class "Default")
      (node (ref "LSP3") (pin "MP") (pinfunction "MP_MP") (pintype "passive"))
      (node (ref "Q4") (pin "D") (pinfunction "D_D") (pintype "passive"))
      (node (ref "R23") (pin "1") (pinfunction "1_1") (pintype "passive"))
    )
    (net (code "74") (name "Net-(LSP4-PadMP)") (class "Default")
      (node (ref "LSP4") (pin "MP") (pinfunction "MP_MP") (pintype "passive"))
      (node (ref "Q5") (pin "D") (pinfunction "D_D") (pintype "passive"))
      (node (ref "R24") (pin "1") (pinfunction "1_1") (pintype "passive"))
    )
    (net (code "75") (name "Net-(LSP5-PadMP)") (class "Default")
      (node (ref "LSP5") (pin "MP") (pinfunction "MP_MP") (pintype "passive"))
      (node (ref "Q6") (pin "D") (pinfunction "D_D") (pintype "passive"))
      (node (ref "R25") (pin "1") (pinfunction "1_1") (pintype "passive"))
    )
    (net (code "76") (name "Net-(LSP6-PadMP)") (class "Default")
      (node (ref "LSP6") (pin "MP") (pinfunction "MP_MP") (pintype "passive"))
      (node (ref "Q7") (pin "D") (pinfunction "D_D") (pintype "passive"))
      (node (ref "R26") (pin "1") (pinfunction "1_1") (pintype "passive"))
    )
    (net (code "77") (name "Net-(LSP7-PadMP)") (class "Default")
      (node (ref "LSP7") (pin "MP") (pinfunction "MP_MP") (pintype "passive"))
      (node (ref "Q8") (pin "D") (pinfunction "D_D") (pintype "passive"))
      (node (ref "R27") (pin "1") (pinfunction "1_1") (pintype "passive"))
    )
    (net (code "78") (name "Net-(LSP8-PadMP)") (class "Default")
      (node (ref "LSP8") (pin "MP") (pinfunction "MP_MP") (pintype "passive"))
      (node (ref "Q9") (pin "D") (pinfunction "D_D") (pintype "passive"))
      (node (ref "R28") (pin "1") (pinfunction "1_1") (pintype "passive"))
    )
    (net (code "79") (name "Net-(LSP9-PadMP)") (class "Default")
      (node (ref "LSP9") (pin "MP") (pinfunction "MP_MP") (pintype "passive"))
      (node (ref "Q10") (pin "D") (pinfunction "D_D") (pintype "passive"))
      (node (ref "R29") (pin "1") (pinfunction "1_1") (pintype "passive"))
    )
    (net (code "80") (name "Net-(LSP10-PadMP)") (class "Default")
      (node (ref "LSP10") (pin "MP") (pinfunction "MP_MP") (pintype "passive"))
      (node (ref "Q11") (pin "D") (pinfunction "D_D") (pintype "passive"))
      (node (ref "R30") (pin "1") (pinfunction "1_1") (pintype "passive"))
    )
    (net (code "81") (name "Net-(LSP11-PadMP)") (class "Default")
      (node (ref "LSP11") (pin "MP") (pinfunction "MP_MP") (pintype "passive"))
      (node (ref "Q12") (pin "D") (pinfunction "D_D") (pintype "passive"))
      (node (ref "R31") (pin "1") (pinfunction "1_1") (pintype "passive"))
    )
    (net (code "82") (name "Net-(LSP12-PadMP)") (class "Default")
      (node (ref "LSP12") (pin "MP") (pinfunction "MP_MP") (pintype "passive"))
      (node (ref "Q13") (pin "D") (pinfunction "D_D") (pintype "passive"))
      (node (ref "R32") (pin "1") (pinfunction "1_1") (pintype "passive"))
    )
    (net (code "83") (name "Net-(LSP13-PadMP)") (class "Default")
      (node (ref "LSP13") (pin "MP") (pinfunction "MP_MP") (pintype "passive"))
      (node (ref "Q14") (pin "D") (pinfunction "D_D") (pintype "passive"))
      (node (ref "R33") (pin "1") (pinfunction "1_1") (pintype "passive"))
    )
    (net (code "84") (name "Net-(LSP14-PadMP)") (class "Default")
      (node (ref "LSP14") (pin "MP") (pinfunction "MP_MP") (pintype "passive"))
      (node (ref "Q15") (pin "D") (pinfunction "D_D") (pintype "passive"))
      (node (ref "R34") (pin "1") (pinfunction "1_1") (pintype "passive"))
    )
    (net (code "85") (name "Net-(LSP15-PadMP)") (class "Default")
      (node (ref "LSP15") (pin "MP") (pinfunction "MP_MP") (pintype "passive"))
      (node (ref "Q16") (pin "D") (pinfunction "D_D") (pintype "passive"))
      (node (ref "R35") (pin "1") (pinfunction "1_1") (pintype "passive"))
    )
    (net (code "86") (name "Net-(LSP16-PadMP)") (class "Default")
      (node (ref "LSP16") (pin "MP") (pinfunction "MP_MP") (pintype "passive"))
      (node (ref "Q17") (pin "D") (pinfunction "D_D") (pintype "passive"))
      (node (ref "R36") (pin "1") (pinfunction "1_1") (pintype "passive"))
    )
    (net (code "87") (name "Net-(LSP_1-PadMP)") (class "Default")
      (node (ref "LSP_1") (pin "MP") (pinfunction "MP_MP") (pintype "passive"))
      (node (ref "LSP_2") (pin "MP") (pinfunction "MP_MP") (pintype "passive"))
      (node (ref "LSP_3") (pin "MP") (pinfunction "MP_MP") (pintype "passive"))
      (node (ref "LSP_4") (pin "MP") (pinfunction "MP_MP") (pintype "passive"))
      (node (ref "R_Z") (pin "1") (pinfunction "1_1") (pintype "passive"))
    )
    (net (code "88") (name "Net-(R2-Pad2)") (class "Default")
      (node (ref "R2") (pin "2") (pinfunction "2_2") (pintype "passive"))
      (node (ref "U$4") (pin "DIO2") (pinfunction "DIO2_DIO2") (pintype "bidirectional"))
    )
    (net (code "89") (name "Net-(R3-Pad1)") (class "Default")
      (node (ref "R3") (pin "1") (pinfunction "1_1") (pintype "passive"))
      (node (ref "U$4") (pin "NRES") (pinfunction "NRES_NRES") (pintype "bidirectional"))
    )
    (net (code "90") (name "Net-(R4-Pad2)") (class "Default")
      (node (ref "R4") (pin "2") (pinfunction "2_2") (pintype "passive"))
      (node (ref "U$4") (pin "SCK") (pinfunction "SCK_SCK") (pintype "input"))
    )
    (net (code "91") (name "Net-(R5-Pad2)") (class "Default")
      (node (ref "R5") (pin "2") (pinfunction "2_2") (pintype "passive"))
      (node (ref "U$4") (pin "SDO") (pinfunction "SDO_SDO") (pintype "output"))
    )
    (net (code "92") (name "Net-(R6-Pad2)") (class "Default")
      (node (ref "R6") (pin "2") (pinfunction "2_2") (pintype "passive"))
      (node (ref "U$4") (pin "SDI") (pinfunction "SDI_SDI") (pintype "input"))
    )
    (net (code "93") (name "RTS") (class "Default")
      (node (ref "IC1") (pin "10") (pinfunction "T2IN_10") (pintype "input"))
      (node (ref "IC2") (pin "4") (pinfunction "PD2(INT0)_4") (pintype "bidirectional"))
    )
    (net (code "94") (name "RX") (class "Default")
      (node (ref "IC1") (pin "12") (pinfunction "R1OUT_12") (pintype "output"))
      (node (ref "IC2") (pin "2") (pinfunction "PD0(RXD)_2") (pintype "bidirectional"))
    )
    (net (code "95") (name "SCK") (class "Default")
      (node (ref "IC2") (pin "19") (pinfunction "PB5(SCK)_19") (pintype "bidirectional"))
      (node (ref "R4") (pin "1") (pinfunction "1_1") (pintype "passive"))
      (node (ref "SV2") (pin "7") (pinfunction "7_7") (pintype "passive"))
    )
    (net (code "96") (name "SHIFT_OE") (class "Default")
      (node (ref "IC2") (pin "24") (pinfunction "PC1(ADC1)_24") (pintype "bidirectional"))
      (node (ref "IC6") (pin "13") (pinfunction "G_13") (pintype "input"))
      (node (ref "IC7") (pin "13") (pinfunction "G_13") (pintype "input"))
      (node (ref "R12") (pin "1") (pinfunction "1_1") (pintype "passive"))
    )
    (net (code "97") (name "SHIFT_RCK") (class "Default")
      (node (ref "IC2") (pin "25") (pinfunction "PC2(ADC2)_25") (pintype "bidirectional"))
      (node (ref "IC6") (pin "12") (pinfunction "RCK_12") (pintype "input"))
      (node (ref "IC7") (pin "12") (pinfunction "RCK_12") (pintype "input"))
    )
    (net (code "98") (name "SHIFT_SCK") (class "Default")
      (node (ref "IC2") (pin "26") (pinfunction "PC3(ADC3)_26") (pintype "bidirectional"))
      (node (ref "IC6") (pin "11") (pinfunction "SCK_11") (pintype "input"))
      (node (ref "IC7") (pin "11") (pinfunction "SCK_11") (pintype "input"))
    )
    (net (code "99") (name "SHIFT_SER") (class "Default")
      (node (ref "IC2") (pin "23") (pinfunction "PC0(ADC0)_23") (pintype "bidirectional"))
      (node (ref "IC6") (pin "14") (pinfunction "SER_14") (pintype "input"))
      (node (ref "R20") (pin "1") (pinfunction "1_1") (pintype "passive"))
    )
    (net (code "100") (name "TX") (class "Default")
      (node (ref "IC1") (pin "11") (pinfunction "T1IN_11") (pintype "input"))
      (node (ref "IC2") (pin "3") (pinfunction "PD1(TXD)_3") (pintype "bidirectional"))
    )
    (net (code "101") (name "V_BATT") (class "Default")
      (node (ref "C13") (pin "+") (pinfunction "+_+") (pintype "passive"))
      (node (ref "C19") (pin "+") (pinfunction "+_+") (pintype "passive"))
      (node (ref "C20") (pin "1") (pinfunction "1_1") (pintype "passive"))
      (node (ref "C25") (pin "1") (pinfunction "1_1") (pintype "passive"))
      (node (ref "D3") (pin "C") (pinfunction "C_C") (pintype "passive"))
      (node (ref "IC4") (pin "6") (pinfunction "VCC_6") (pintype "bidirectional"))
      (node (ref "IC8") (pin "3") (pinfunction "IN_3") (pintype "input"))
      (node (ref "PWR_SW2") (pin "MP") (pinfunction "MP_MP") (pintype "passive"))
      (node (ref "R17") (pin "1") (pinfunction "1_1") (pintype "passive"))
      (node (ref "R18") (pin "2") (pinfunction "2_2") (pintype "passive"))
      (node (ref "U$3") (pin "VIN") (pinfunction "VIN_VIN") (pintype "bidirectional"))
    )
    (net (code "102") (name "unconnected-(IC2-PD4(XCK{slash}T0)-Pad6)") (class "Default")
      (node (ref "IC2") (pin "6") (pinfunction "PD4(XCK/T0)_6") (pintype "bidirectional"))
    )
    (net (code "103") (name "unconnected-(IC7A-QH*-Pad9)") (class "Default")
      (node (ref "IC7") (pin "9") (pinfunction "QH*_9") (pintype "tri_state"))
    )
    (net (code "104") (name "unconnected-(SV2-Pad3)") (class "Default")
      (node (ref "SV2") (pin "3") (pinfunction "3_3") (pintype "passive"))
    )
    (net (code "105") (name "unconnected-(U$4-PadDIO0)") (class "Default")
      (node (ref "U$4") (pin "DIO0") (pinfunction "DIO0_DIO0") (pintype "bidirectional"))
    )
    (net (code "106") (name "unconnected-(U$4-PadDIO1)") (class "Default")
      (node (ref "U$4") (pin "DIO1") (pinfunction "DIO1_DIO1") (pintype "bidirectional"))
    )
    (net (code "107") (name "unconnected-(U$4-PadDIO3)") (class "Default")
      (node (ref "U$4") (pin "DIO3") (pinfunction "DIO3_DIO3") (pintype "bidirectional"))
    )
    (net (code "108") (name "unconnected-(U$4-PadDIO5)") (class "Default")
      (node (ref "U$4") (pin "DIO5") (pinfunction "DIO5_DIO5") (pintype "bidirectional"))
    )
    (net (code "109") (name "{slash}RST") (class "Default")
      (node (ref "C7") (pin "1") (pinfunction "1_1") (pintype "passive"))
      (node (ref "IC2") (pin "1") (pinfunction "PC6(/RESET)_1") (pintype "bidirectional"))
      (node (ref "R1") (pin "1") (pinfunction "1_1") (pintype "passive"))
      (node (ref "SV2") (pin "5") (pinfunction "5_5") (pintype "passive"))
    )
  )
)
